# ada2.net
KiCad netlist of a schematic drawn in EAGLE
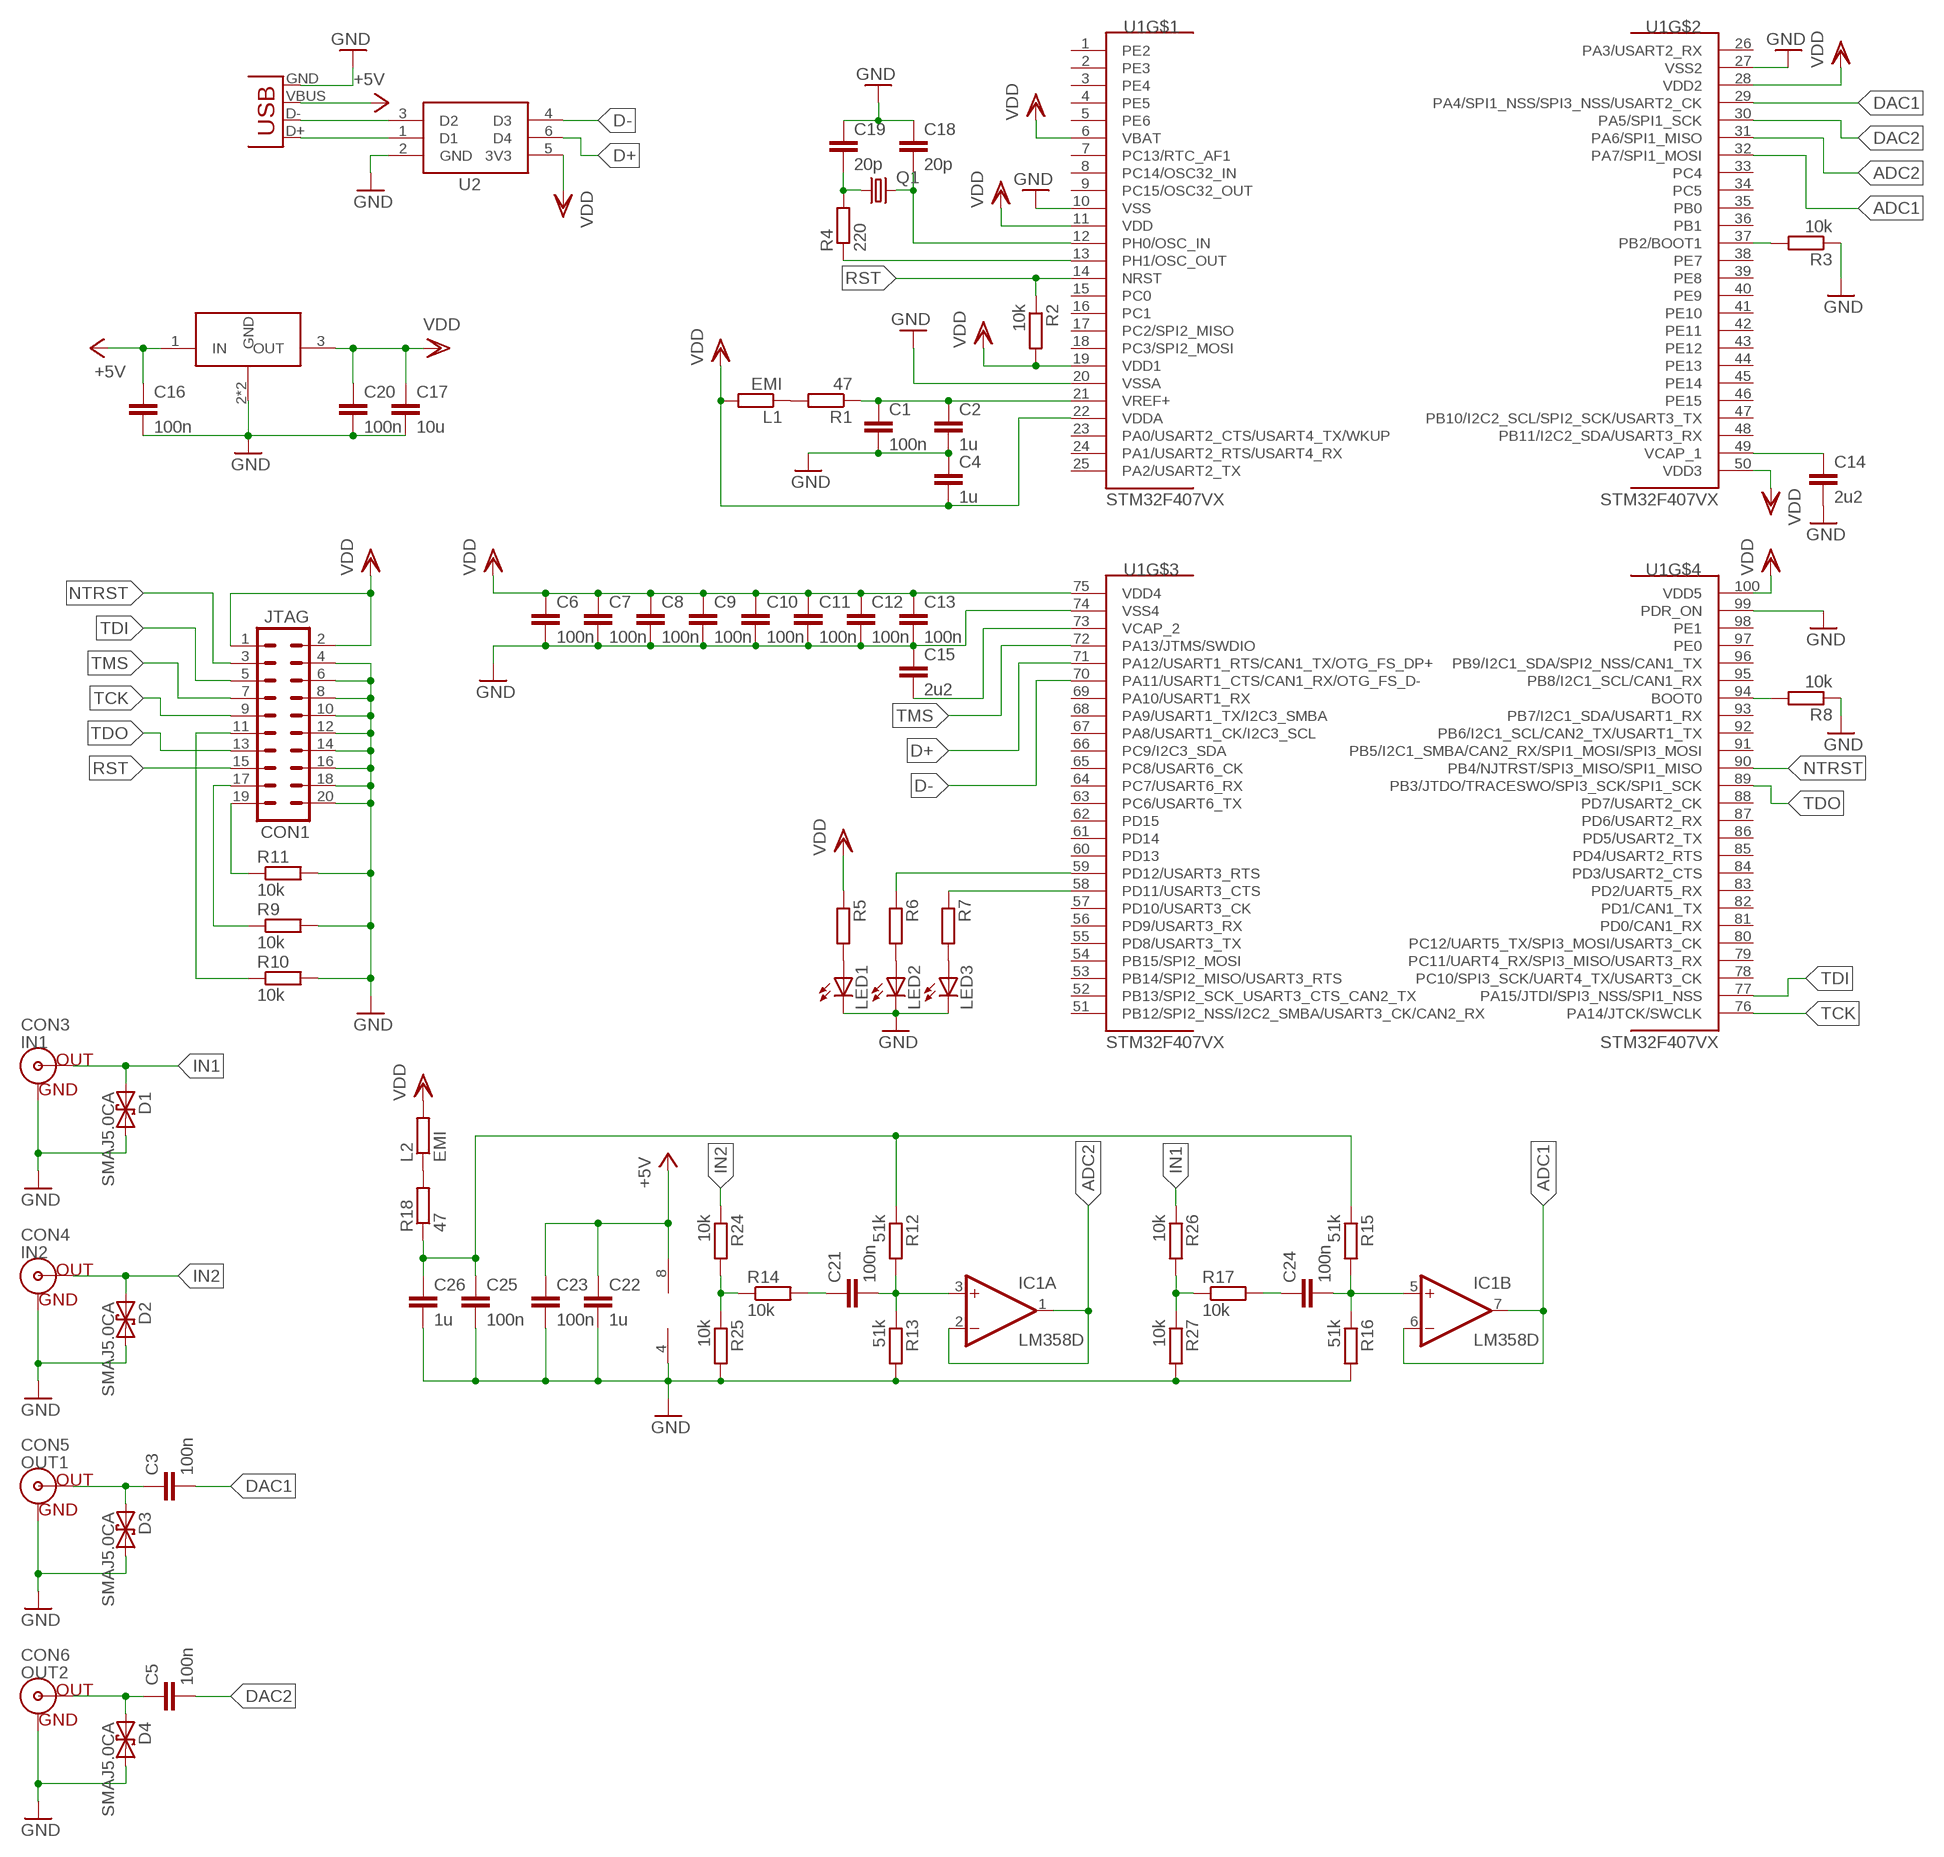
[diagram p0: schematic, sheet 1]

(export (version "E")
  (design (tool "Eeschema 10.0.6"))
  (components
    (comp (ref "C1")
      (value "100n")
      (footprint "eagle-import:C0603K")
      (libsource (lib "eagle-import") (part "C-EUC0603K"))
    )
    (comp (ref "C2")
      (value "1u")
      (footprint "eagle-import:C0603K")
      (libsource (lib "eagle-import") (part "C-EUC0603K"))
    )
    (comp (ref "C3")
      (value "100n")
      (footprint "eagle-import:C0603K")
      (libsource (lib "eagle-import") (part "C-EUC0603K"))
    )
    (comp (ref "C4")
      (value "1u")
      (footprint "eagle-import:C0603K")
      (libsource (lib "eagle-import") (part "C-EUC0603K"))
    )
    (comp (ref "C5")
      (value "100n")
      (footprint "eagle-import:C0603K")
      (libsource (lib "eagle-import") (part "C-EUC0603K"))
    )
    (comp (ref "C6")
      (value "100n")
      (footprint "eagle-import:C0603K")
      (libsource (lib "eagle-import") (part "C-EUC0603K"))
    )
    (comp (ref "C7")
      (value "100n")
      (footprint "eagle-import:C0603K")
      (libsource (lib "eagle-import") (part "C-EUC0603K"))
    )
    (comp (ref "C8")
      (value "100n")
      (footprint "eagle-import:C0603K")
      (libsource (lib "eagle-import") (part "C-EUC0603K"))
    )
    (comp (ref "C9")
      (value "100n")
      (footprint "eagle-import:C0603K")
      (libsource (lib "eagle-import") (part "C-EUC0603K"))
    )
    (comp (ref "C10")
      (value "100n")
      (footprint "eagle-import:C0603K")
      (libsource (lib "eagle-import") (part "C-EUC0603K"))
    )
    (comp (ref "C11")
      (value "100n")
      (footprint "eagle-import:C0603K")
      (libsource (lib "eagle-import") (part "C-EUC0603K"))
    )
    (comp (ref "C12")
      (value "100n")
      (footprint "eagle-import:C0603K")
      (libsource (lib "eagle-import") (part "C-EUC0603K"))
    )
    (comp (ref "C13")
      (value "100n")
      (footprint "eagle-import:C0603K")
      (libsource (lib "eagle-import") (part "C-EUC0603K"))
    )
    (comp (ref "C14")
      (value "2u2")
      (footprint "eagle-import:C0603K")
      (libsource (lib "eagle-import") (part "C-EUC0603K"))
    )
    (comp (ref "C15")
      (value "2u2")
      (footprint "eagle-import:C0603K")
      (libsource (lib "eagle-import") (part "C-EUC0603K"))
    )
    (comp (ref "C16")
      (value "100n")
      (footprint "eagle-import:C0603K")
      (libsource (lib "eagle-import") (part "C-EUC0603K"))
    )
    (comp (ref "C17")
      (value "10u")
      (footprint "eagle-import:C0603K")
      (libsource (lib "eagle-import") (part "C-EUC0603K"))
    )
    (comp (ref "C18")
      (value "20p")
      (footprint "eagle-import:C0603K")
      (libsource (lib "eagle-import") (part "C-EUC0603K"))
    )
    (comp (ref "C19")
      (value "20p")
      (footprint "eagle-import:C0603K")
      (libsource (lib "eagle-import") (part "C-EUC0603K"))
    )
    (comp (ref "C20")
      (value "100n")
      (footprint "eagle-import:C0603K")
      (libsource (lib "eagle-import") (part "C-EUC0603K"))
    )
    (comp (ref "C21")
      (value "100n")
      (footprint "eagle-import:C0603K")
      (libsource (lib "eagle-import") (part "C-EUC0603K"))
    )
    (comp (ref "C22")
      (value "1u")
      (footprint "eagle-import:C0603K")
      (libsource (lib "eagle-import") (part "C-EUC0603K"))
    )
    (comp (ref "C23")
      (value "100n")
      (footprint "eagle-import:C0603K")
      (libsource (lib "eagle-import") (part "C-EUC0603K"))
    )
    (comp (ref "C24")
      (value "100n")
      (footprint "eagle-import:C0603K")
      (libsource (lib "eagle-import") (part "C-EUC0603K"))
    )
    (comp (ref "C25")
      (value "100n")
      (footprint "eagle-import:C0603K")
      (libsource (lib "eagle-import") (part "C-EUC0603K"))
    )
    (comp (ref "C26")
      (value "1u")
      (footprint "eagle-import:C0603K")
      (libsource (lib "eagle-import") (part "C-EUC0603K"))
    )
    (comp (ref "CON1")
      (value "JTAG")
      (footprint "eagle-import:ML20")
      (libsource (lib "eagle-import") (part "ML20"))
    )
    (comp (ref "CON2")
      (value "USB-B")
      (footprint "eagle-import:USB-B-PTH")
      (libsource (lib "eagle-import") (part "USBPTH"))
    )
    (comp (ref "CON3")
      (value "IN1")
      (footprint "eagle-import:BNC")
      (libsource (lib "eagle-import") (part "BNCPTH"))
    )
    (comp (ref "CON4")
      (value "IN2")
      (footprint "eagle-import:BNC")
      (libsource (lib "eagle-import") (part "BNCPTH"))
    )
    (comp (ref "CON5")
      (value "OUT1")
      (footprint "eagle-import:BNC")
      (libsource (lib "eagle-import") (part "BNCPTH"))
    )
    (comp (ref "CON6")
      (value "OUT2")
      (footprint "eagle-import:BNC")
      (libsource (lib "eagle-import") (part "BNCPTH"))
    )
    (comp (ref "D1")
      (value "SMAJ5.0CA")
      (footprint "eagle-import:SMA-DIODE")
      (libsource (lib "eagle-import") (part "TVS"))
    )
    (comp (ref "D2")
      (value "SMAJ5.0CA")
      (footprint "eagle-import:SMA-DIODE")
      (libsource (lib "eagle-import") (part "TVS"))
    )
    (comp (ref "D3")
      (value "SMAJ5.0CA")
      (footprint "eagle-import:SMA-DIODE")
      (libsource (lib "eagle-import") (part "TVS"))
    )
    (comp (ref "D4")
      (value "SMAJ5.0CA")
      (footprint "eagle-import:SMA-DIODE")
      (libsource (lib "eagle-import") (part "TVS"))
    )
    (comp (ref "IC1")
      (value "LM358D")
      (footprint "eagle-import:SO08")
      (libsource (lib "eagle-import") (part "LM358D"))
    )
    (comp (ref "L1")
      (value "EMI")
      (footprint "eagle-import:R0603")
      (libsource (lib "eagle-import") (part "R-EU_R0603"))
    )
    (comp (ref "L2")
      (value "EMI")
      (footprint "eagle-import:R0603")
      (libsource (lib "eagle-import") (part "R-EU_R0603"))
    )
    (comp (ref "LED1")
      (value "KONTROLKA_LED")
      (footprint "eagle-import:KONTROLKA_LED")
      (libsource (lib "eagle-import") (part "KONTROLKA_LED"))
    )
    (comp (ref "LED2")
      (value "KONTROLKA_LED")
      (footprint "eagle-import:KONTROLKA_LED")
      (libsource (lib "eagle-import") (part "KONTROLKA_LED"))
    )
    (comp (ref "LED3")
      (value "KONTROLKA_LED")
      (footprint "eagle-import:KONTROLKA_LED")
      (libsource (lib "eagle-import") (part "KONTROLKA_LED"))
    )
    (comp (ref "Q1")
      (value "CRYSTALHC49UP")
      (footprint "eagle-import:HC49UP")
      (libsource (lib "eagle-import") (part "CRYSTALHC49UP"))
    )
    (comp (ref "R1")
      (value "47")
      (footprint "eagle-import:R0603")
      (libsource (lib "eagle-import") (part "R-EU_R0603"))
    )
    (comp (ref "R2")
      (value "10k")
      (footprint "eagle-import:R0603")
      (libsource (lib "eagle-import") (part "R-EU_R0603"))
    )
    (comp (ref "R3")
      (value "10k")
      (footprint "eagle-import:R0603")
      (libsource (lib "eagle-import") (part "R-EU_R0603"))
    )
    (comp (ref "R4")
      (value "220")
      (footprint "eagle-import:R0603")
      (libsource (lib "eagle-import") (part "R-EU_R0603"))
    )
    (comp (ref "R5")
      (value "R-EU_R0603")
      (footprint "eagle-import:R0603")
      (libsource (lib "eagle-import") (part "R-EU_R0603"))
    )
    (comp (ref "R6")
      (value "R-EU_R0603")
      (footprint "eagle-import:R0603")
      (libsource (lib "eagle-import") (part "R-EU_R0603"))
    )
    (comp (ref "R7")
      (value "R-EU_R0603")
      (footprint "eagle-import:R0603")
      (libsource (lib "eagle-import") (part "R-EU_R0603"))
    )
    (comp (ref "R8")
      (value "10k")
      (footprint "eagle-import:R0603")
      (libsource (lib "eagle-import") (part "R-EU_R0603"))
    )
    (comp (ref "R9")
      (value "10k")
      (footprint "eagle-import:R0603")
      (libsource (lib "eagle-import") (part "R-EU_R0603"))
    )
    (comp (ref "R10")
      (value "10k")
      (footprint "eagle-import:R0603")
      (libsource (lib "eagle-import") (part "R-EU_R0603"))
    )
    (comp (ref "R11")
      (value "10k")
      (footprint "eagle-import:R0603")
      (libsource (lib "eagle-import") (part "R-EU_R0603"))
    )
    (comp (ref "R12")
      (value "51k")
      (footprint "eagle-import:R0603")
      (libsource (lib "eagle-import") (part "R-EU_R0603"))
    )
    (comp (ref "R13")
      (value "51k")
      (footprint "eagle-import:R0603")
      (libsource (lib "eagle-import") (part "R-EU_R0603"))
    )
    (comp (ref "R14")
      (value "10k")
      (footprint "eagle-import:R0603")
      (libsource (lib "eagle-import") (part "R-EU_R0603"))
    )
    (comp (ref "R15")
      (value "51k")
      (footprint "eagle-import:R0603")
      (libsource (lib "eagle-import") (part "R-EU_R0603"))
    )
    (comp (ref "R16")
      (value "51k")
      (footprint "eagle-import:R0603")
      (libsource (lib "eagle-import") (part "R-EU_R0603"))
    )
    (comp (ref "R17")
      (value "10k")
      (footprint "eagle-import:R0603")
      (libsource (lib "eagle-import") (part "R-EU_R0603"))
    )
    (comp (ref "R18")
      (value "47")
      (footprint "eagle-import:R0603")
      (libsource (lib "eagle-import") (part "R-EU_R0603"))
    )
    (comp (ref "R24")
      (value "10k")
      (footprint "eagle-import:R0603")
      (libsource (lib "eagle-import") (part "R-EU_R0603"))
    )
    (comp (ref "R25")
      (value "10k")
      (footprint "eagle-import:R0603")
      (libsource (lib "eagle-import") (part "R-EU_R0603"))
    )
    (comp (ref "R26")
      (value "10k")
      (footprint "eagle-import:R0603")
      (libsource (lib "eagle-import") (part "R-EU_R0603"))
    )
    (comp (ref "R27")
      (value "10k")
      (footprint "eagle-import:R0603")
      (libsource (lib "eagle-import") (part "R-EU_R0603"))
    )
    (comp (ref "U1")
      (value "STM32F407VX")
      (footprint "eagle-import:LQFP100")
      (libsource (lib "eagle-import") (part "STM32F407VX"))
    )
    (comp (ref "U2")
      (value "USBUF01W6")
      (footprint "eagle-import:SOT363")
      (libsource (lib "eagle-import") (part "USBUF01W6"))
    )
    (comp (ref "U3")
      (value "MCP1703")
      (footprint "eagle-import:SOT223")
      (libsource (lib "eagle-import") (part "MCP1703"))
    )
  )
  (nets
    (net (code "1") (name "+5V") (class "Default")
      (node (ref "C16") (pin "1") (pinfunction "1_1") (pintype "passive"))
      (node (ref "C22") (pin "1") (pinfunction "1_1") (pintype "passive"))
      (node (ref "C23") (pin "1") (pinfunction "1_1") (pintype "passive"))
      (node (ref "CON2") (pin "VBUS") (pinfunction "VBUS_VBUS") (pintype "bidirectional"))
      (node (ref "IC1") (pin "8") (pinfunction "V+_8") (pintype "power_in"))
      (node (ref "U3") (pin "1") (pinfunction "IN_1") (pintype "bidirectional"))
    )
    (net (code "2") (name "ADC1") (class "Default")
      (node (ref "IC1") (pin "6") (pinfunction "-IN_6") (pintype "input"))
      (node (ref "IC1") (pin "7") (pinfunction "OUT_7") (pintype "output"))
      (node (ref "U1") (pin "32") (pinfunction "PA7/SPI1_MOSI_32") (pintype "bidirectional"))
    )
    (net (code "3") (name "ADC2") (class "Default")
      (node (ref "IC1") (pin "1") (pinfunction "OUT_1") (pintype "output"))
      (node (ref "IC1") (pin "2") (pinfunction "-IN_2") (pintype "input"))
      (node (ref "U1") (pin "31") (pinfunction "PA6/SPI1_MISO_31") (pintype "bidirectional"))
    )
    (net (code "4") (name "D+") (class "Default")
      (node (ref "U1") (pin "71") (pinfunction "PA12/USART1_RTS/CAN1_TX/OTG_FS_DP+_71") (pintype "bidirectional"))
      (node (ref "U2") (pin "6") (pinfunction "D4_6") (pintype "bidirectional"))
    )
    (net (code "5") (name "D-") (class "Default")
      (node (ref "U1") (pin "70") (pinfunction "PA11/USART1_CTS/CAN1_RX/OTG_FS_D-_70") (pintype "bidirectional"))
      (node (ref "U2") (pin "4") (pinfunction "D3_4") (pintype "bidirectional"))
    )
    (net (code "6") (name "DAC1") (class "Default")
      (node (ref "C3") (pin "2") (pinfunction "2_2") (pintype "passive"))
      (node (ref "U1") (pin "29") (pinfunction "PA4/SPI1_NSS/SPI3_NSS/USART2_CK_29") (pintype "bidirectional"))
    )
    (net (code "7") (name "DAC2") (class "Default")
      (node (ref "C5") (pin "2") (pinfunction "2_2") (pintype "passive"))
      (node (ref "U1") (pin "30") (pinfunction "PA5/SPI1_SCK_30") (pintype "bidirectional"))
    )
    (net (code "8") (name "GND") (class "Default")
      (node (ref "C1") (pin "2") (pinfunction "2_2") (pintype "passive"))
      (node (ref "C10") (pin "2") (pinfunction "2_2") (pintype "passive"))
      (node (ref "C11") (pin "2") (pinfunction "2_2") (pintype "passive"))
      (node (ref "C12") (pin "2") (pinfunction "2_2") (pintype "passive"))
      (node (ref "C13") (pin "2") (pinfunction "2_2") (pintype "passive"))
      (node (ref "C14") (pin "2") (pinfunction "2_2") (pintype "passive"))
      (node (ref "C15") (pin "1") (pinfunction "1_1") (pintype "passive"))
      (node (ref "C16") (pin "2") (pinfunction "2_2") (pintype "passive"))
      (node (ref "C17") (pin "2") (pinfunction "2_2") (pintype "passive"))
      (node (ref "C18") (pin "1") (pinfunction "1_1") (pintype "passive"))
      (node (ref "C19") (pin "1") (pinfunction "1_1") (pintype "passive"))
      (node (ref "C2") (pin "2") (pinfunction "2_2") (pintype "passive"))
      (node (ref "C20") (pin "2") (pinfunction "2_2") (pintype "passive"))
      (node (ref "C22") (pin "2") (pinfunction "2_2") (pintype "passive"))
      (node (ref "C23") (pin "2") (pinfunction "2_2") (pintype "passive"))
      (node (ref "C25") (pin "2") (pinfunction "2_2") (pintype "passive"))
      (node (ref "C26") (pin "2") (pinfunction "2_2") (pintype "passive"))
      (node (ref "C4") (pin "1") (pinfunction "1_1") (pintype "passive"))
      (node (ref "C6") (pin "2") (pinfunction "2_2") (pintype "passive"))
      (node (ref "C7") (pin "2") (pinfunction "2_2") (pintype "passive"))
      (node (ref "C8") (pin "2") (pinfunction "2_2") (pintype "passive"))
      (node (ref "C9") (pin "2") (pinfunction "2_2") (pintype "passive"))
      (node (ref "CON1") (pin "10") (pinfunction "10_10") (pintype "passive"))
      (node (ref "CON1") (pin "12") (pinfunction "12_12") (pintype "passive"))
      (node (ref "CON1") (pin "14") (pinfunction "14_14") (pintype "passive"))
      (node (ref "CON1") (pin "16") (pinfunction "16_16") (pintype "passive"))
      (node (ref "CON1") (pin "18") (pinfunction "18_18") (pintype "passive"))
      (node (ref "CON1") (pin "20") (pinfunction "20_20") (pintype "passive"))
      (node (ref "CON1") (pin "4") (pinfunction "4_4") (pintype "passive"))
      (node (ref "CON1") (pin "6") (pinfunction "6_6") (pintype "passive"))
      (node (ref "CON1") (pin "8") (pinfunction "8_8") (pintype "passive"))
      (node (ref "CON2") (pin "GND") (pinfunction "GND_GND") (pintype "bidirectional"))
      (node (ref "CON3") (pin "GND") (pinfunction "GND_GND") (pintype "bidirectional"))
      (node (ref "CON4") (pin "GND") (pinfunction "GND_GND") (pintype "bidirectional"))
      (node (ref "CON5") (pin "GND") (pinfunction "GND_GND") (pintype "bidirectional"))
      (node (ref "CON6") (pin "GND") (pinfunction "GND_GND") (pintype "bidirectional"))
      (node (ref "D1") (pin "C") (pinfunction "2_C") (pintype "passive"))
      (node (ref "D2") (pin "C") (pinfunction "2_C") (pintype "passive"))
      (node (ref "D3") (pin "C") (pinfunction "2_C") (pintype "passive"))
      (node (ref "D4") (pin "C") (pinfunction "2_C") (pintype "passive"))
      (node (ref "IC1") (pin "4") (pinfunction "V-_4") (pintype "power_in"))
      (node (ref "LED1") (pin "K") (pinfunction "C_K") (pintype "passive"))
      (node (ref "LED2") (pin "K") (pinfunction "C_K") (pintype "passive"))
      (node (ref "LED3") (pin "K") (pinfunction "C_K") (pintype "passive"))
      (node (ref "R10") (pin "2") (pinfunction "2_2") (pintype "passive"))
      (node (ref "R11") (pin "2") (pinfunction "2_2") (pintype "passive"))
      (node (ref "R13") (pin "2") (pinfunction "2_2") (pintype "passive"))
      (node (ref "R16") (pin "2") (pinfunction "2_2") (pintype "passive"))
      (node (ref "R25") (pin "2") (pinfunction "2_2") (pintype "passive"))
      (node (ref "R27") (pin "2") (pinfunction "2_2") (pintype "passive"))
      (node (ref "R3") (pin "1") (pinfunction "1_1") (pintype "passive"))
      (node (ref "R8") (pin "1") (pinfunction "1_1") (pintype "passive"))
      (node (ref "R9") (pin "2") (pinfunction "2_2") (pintype "passive"))
      (node (ref "U1") (pin "10") (pinfunction "VSS_10") (pintype "bidirectional"))
      (node (ref "U1") (pin "20") (pinfunction "VSSA_20") (pintype "bidirectional"))
      (node (ref "U1") (pin "27") (pinfunction "VSS2_27") (pintype "bidirectional"))
      (node (ref "U1") (pin "74") (pinfunction "VSS4_74") (pintype "bidirectional"))
      (node (ref "U1") (pin "99") (pinfunction "PDR_ON_99") (pintype "bidirectional"))
      (node (ref "U2") (pin "2") (pinfunction "GND_2") (pintype "bidirectional"))
      (node (ref "U3") (pin "2") (pinfunction "GND_2") (pintype "bidirectional"))
      (node (ref "U3") (pin "2@2") (pinfunction "GND_2@2") (pintype "bidirectional"))
    )
    (net (code "9") (name "IN1") (class "Default")
      (node (ref "CON3") (pin "S") (pinfunction "OUT_S") (pintype "bidirectional"))
      (node (ref "D1") (pin "A") (pinfunction "1_A") (pintype "passive"))
      (node (ref "R26") (pin "1") (pinfunction "1_1") (pintype "passive"))
    )
    (net (code "10") (name "IN2") (class "Default")
      (node (ref "CON4") (pin "S") (pinfunction "OUT_S") (pintype "bidirectional"))
      (node (ref "D2") (pin "A") (pinfunction "1_A") (pintype "passive"))
      (node (ref "R24") (pin "1") (pinfunction "1_1") (pintype "passive"))
    )
    (net (code "11") (name "NTRST") (class "Default")
      (node (ref "CON1") (pin "3") (pinfunction "3_3") (pintype "passive"))
      (node (ref "U1") (pin "90") (pinfunction "PB4/NJTRST/SPI3_MISO/SPI1_MISO_90") (pintype "bidirectional"))
    )
    (net (code "12") (name "Net-(C19-Pad2)") (class "Default")
      (node (ref "C19") (pin "2") (pinfunction "2_2") (pintype "passive"))
      (node (ref "Q1") (pin "1") (pinfunction "1_1") (pintype "passive"))
      (node (ref "R4") (pin "2") (pinfunction "2_2") (pintype "passive"))
    )
    (net (code "13") (name "Net-(C21-Pad1)") (class "Default")
      (node (ref "C21") (pin "1") (pinfunction "1_1") (pintype "passive"))
      (node (ref "R14") (pin "2") (pinfunction "2_2") (pintype "passive"))
    )
    (net (code "14") (name "Net-(C24-Pad1)") (class "Default")
      (node (ref "C24") (pin "1") (pinfunction "1_1") (pintype "passive"))
      (node (ref "R17") (pin "2") (pinfunction "2_2") (pintype "passive"))
    )
    (net (code "15") (name "Net-(C25-Pad1)") (class "Default")
      (node (ref "C25") (pin "1") (pinfunction "1_1") (pintype "passive"))
      (node (ref "C26") (pin "1") (pinfunction "1_1") (pintype "passive"))
      (node (ref "R12") (pin "1") (pinfunction "1_1") (pintype "passive"))
      (node (ref "R15") (pin "1") (pinfunction "1_1") (pintype "passive"))
      (node (ref "R18") (pin "1") (pinfunction "1_1") (pintype "passive"))
    )
    (net (code "16") (name "Net-(CON1-Pad11)") (class "Default")
      (node (ref "CON1") (pin "11") (pinfunction "11_11") (pintype "passive"))
      (node (ref "R10") (pin "1") (pinfunction "1_1") (pintype "passive"))
    )
    (net (code "17") (name "Net-(CON1-Pad17)") (class "Default")
      (node (ref "CON1") (pin "17") (pinfunction "17_17") (pintype "passive"))
      (node (ref "R9") (pin "1") (pinfunction "1_1") (pintype "passive"))
    )
    (net (code "18") (name "Net-(CON1-Pad19)") (class "Default")
      (node (ref "CON1") (pin "19") (pinfunction "19_19") (pintype "passive"))
      (node (ref "R11") (pin "1") (pinfunction "1_1") (pintype "passive"))
    )
    (net (code "19") (name "Net-(CON5-OUT)") (class "Default")
      (node (ref "C3") (pin "1") (pinfunction "1_1") (pintype "passive"))
      (node (ref "CON5") (pin "S") (pinfunction "OUT_S") (pintype "bidirectional"))
      (node (ref "D3") (pin "A") (pinfunction "1_A") (pintype "passive"))
    )
    (net (code "20") (name "Net-(CON6-OUT)") (class "Default")
      (node (ref "C5") (pin "1") (pinfunction "1_1") (pintype "passive"))
      (node (ref "CON6") (pin "S") (pinfunction "OUT_S") (pintype "bidirectional"))
      (node (ref "D4") (pin "A") (pinfunction "1_A") (pintype "passive"))
    )
    (net (code "21") (name "Net-(IC1A-+IN)") (class "Default")
      (node (ref "C21") (pin "2") (pinfunction "2_2") (pintype "passive"))
      (node (ref "IC1") (pin "3") (pinfunction "+IN_3") (pintype "input"))
      (node (ref "R12") (pin "2") (pinfunction "2_2") (pintype "passive"))
      (node (ref "R13") (pin "1") (pinfunction "1_1") (pintype "passive"))
    )
    (net (code "22") (name "Net-(IC1B-+IN)") (class "Default")
      (node (ref "C24") (pin "2") (pinfunction "2_2") (pintype "passive"))
      (node (ref "IC1") (pin "5") (pinfunction "+IN_5") (pintype "input"))
      (node (ref "R15") (pin "2") (pinfunction "2_2") (pintype "passive"))
      (node (ref "R16") (pin "1") (pinfunction "1_1") (pintype "passive"))
    )
    (net (code "23") (name "Net-(L1-Pad1)") (class "Default")
      (node (ref "L1") (pin "1") (pinfunction "1_1") (pintype "passive"))
      (node (ref "R1") (pin "2") (pinfunction "2_2") (pintype "passive"))
    )
    (net (code "24") (name "Net-(L2-Pad1)") (class "Default")
      (node (ref "L2") (pin "1") (pinfunction "1_1") (pintype "passive"))
      (node (ref "R18") (pin "2") (pinfunction "2_2") (pintype "passive"))
    )
    (net (code "25") (name "Net-(LED1-PadA)") (class "Default")
      (node (ref "LED1") (pin "A") (pinfunction "A_A") (pintype "passive"))
      (node (ref "R5") (pin "2") (pinfunction "2_2") (pintype "passive"))
    )
    (net (code "26") (name "Net-(LED2-PadA)") (class "Default")
      (node (ref "LED2") (pin "A") (pinfunction "A_A") (pintype "passive"))
      (node (ref "R6") (pin "2") (pinfunction "2_2") (pintype "passive"))
    )
    (net (code "27") (name "Net-(LED3-PadA)") (class "Default")
      (node (ref "LED3") (pin "A") (pinfunction "A_A") (pintype "passive"))
      (node (ref "R7") (pin "2") (pinfunction "2_2") (pintype "passive"))
    )
    (net (code "28") (name "Net-(R14-Pad1)") (class "Default")
      (node (ref "R14") (pin "1") (pinfunction "1_1") (pintype "passive"))
      (node (ref "R24") (pin "2") (pinfunction "2_2") (pintype "passive"))
      (node (ref "R25") (pin "1") (pinfunction "1_1") (pintype "passive"))
    )
    (net (code "29") (name "Net-(R17-Pad1)") (class "Default")
      (node (ref "R17") (pin "1") (pinfunction "1_1") (pintype "passive"))
      (node (ref "R26") (pin "2") (pinfunction "2_2") (pintype "passive"))
      (node (ref "R27") (pin "1") (pinfunction "1_1") (pintype "passive"))
    )
    (net (code "30") (name "Net-(U1A-PH0{slash}OSC_IN)") (class "Default")
      (node (ref "C18") (pin "2") (pinfunction "2_2") (pintype "passive"))
      (node (ref "Q1") (pin "2") (pinfunction "2_2") (pintype "passive"))
      (node (ref "U1") (pin "12") (pinfunction "PH0/OSC_IN_12") (pintype "bidirectional"))
    )
    (net (code "31") (name "Net-(U1A-PH1{slash}OSC_OUT)") (class "Default")
      (node (ref "R4") (pin "1") (pinfunction "1_1") (pintype "passive"))
      (node (ref "U1") (pin "13") (pinfunction "PH1/OSC_OUT_13") (pintype "bidirectional"))
    )
    (net (code "32") (name "Net-(U1A-VREF+)") (class "Default")
      (node (ref "C1") (pin "1") (pinfunction "1_1") (pintype "passive"))
      (node (ref "C2") (pin "1") (pinfunction "1_1") (pintype "passive"))
      (node (ref "R1") (pin "1") (pinfunction "1_1") (pintype "passive"))
      (node (ref "U1") (pin "21") (pinfunction "VREF+_21") (pintype "bidirectional"))
    )
    (net (code "33") (name "Net-(U1B-PB2{slash}BOOT1)") (class "Default")
      (node (ref "R3") (pin "2") (pinfunction "2_2") (pintype "passive"))
      (node (ref "U1") (pin "37") (pinfunction "PB2/BOOT1_37") (pintype "bidirectional"))
    )
    (net (code "34") (name "Net-(U1B-VCAP_1)") (class "Default")
      (node (ref "C14") (pin "1") (pinfunction "1_1") (pintype "passive"))
      (node (ref "U1") (pin "49") (pinfunction "VCAP_1_49") (pintype "bidirectional"))
    )
    (net (code "35") (name "Net-(U1C-PD11{slash}USART3_CTS)") (class "Default")
      (node (ref "R7") (pin "1") (pinfunction "1_1") (pintype "passive"))
      (node (ref "U1") (pin "58") (pinfunction "PD11/USART3_CTS_58") (pintype "bidirectional"))
    )
    (net (code "36") (name "Net-(U1C-PD12{slash}USART3_RTS)") (class "Default")
      (node (ref "R6") (pin "1") (pinfunction "1_1") (pintype "passive"))
      (node (ref "U1") (pin "59") (pinfunction "PD12/USART3_RTS_59") (pintype "bidirectional"))
    )
    (net (code "37") (name "Net-(U1C-VCAP_2)") (class "Default")
      (node (ref "C15") (pin "2") (pinfunction "2_2") (pintype "passive"))
      (node (ref "U1") (pin "73") (pinfunction "VCAP_2_73") (pintype "bidirectional"))
    )
    (net (code "38") (name "Net-(U1D-BOOT0)") (class "Default")
      (node (ref "R8") (pin "2") (pinfunction "2_2") (pintype "passive"))
      (node (ref "U1") (pin "94") (pinfunction "BOOT0_94") (pintype "bidirectional"))
    )
    (net (code "39") (name "Net-(U2-D1)") (class "Default")
      (node (ref "CON2") (pin "D+") (pinfunction "D+_D+") (pintype "bidirectional"))
      (node (ref "U2") (pin "1") (pinfunction "D1_1") (pintype "bidirectional"))
    )
    (net (code "40") (name "Net-(U2-D2)") (class "Default")
      (node (ref "CON2") (pin "D-") (pinfunction "D-_D-") (pintype "bidirectional"))
      (node (ref "U2") (pin "3") (pinfunction "D2_3") (pintype "bidirectional"))
    )
    (net (code "41") (name "RST") (class "Default")
      (node (ref "CON1") (pin "15") (pinfunction "15_15") (pintype "passive"))
      (node (ref "R2") (pin "1") (pinfunction "1_1") (pintype "passive"))
      (node (ref "U1") (pin "14") (pinfunction "NRST_14") (pintype "bidirectional"))
    )
    (net (code "42") (name "TCK") (class "Default")
      (node (ref "CON1") (pin "9") (pinfunction "9_9") (pintype "passive"))
      (node (ref "U1") (pin "76") (pinfunction "PA14/JTCK/SWCLK_76") (pintype "bidirectional"))
    )
    (net (code "43") (name "TDI") (class "Default")
      (node (ref "CON1") (pin "5") (pinfunction "5_5") (pintype "passive"))
      (node (ref "U1") (pin "77") (pinfunction "PA15/JTDI/SPI3_NSS/SPI1_NSS_77") (pintype "bidirectional"))
    )
    (net (code "44") (name "TDO") (class "Default")
      (node (ref "CON1") (pin "13") (pinfunction "13_13") (pintype "passive"))
      (node (ref "U1") (pin "89") (pinfunction "PB3/JTDO/TRACESWO/SPI3_SCK/SPI1_SCK_89") (pintype "bidirectional"))
    )
    (net (code "45") (name "TMS") (class "Default")
      (node (ref "CON1") (pin "7") (pinfunction "7_7") (pintype "passive"))
      (node (ref "U1") (pin "72") (pinfunction "PA13/JTMS/SWDIO_72") (pintype "bidirectional"))
    )
    (net (code "46") (name "VDD") (class "Default")
      (node (ref "C10") (pin "1") (pinfunction "1_1") (pintype "passive"))
      (node (ref "C11") (pin "1") (pinfunction "1_1") (pintype "passive"))
      (node (ref "C12") (pin "1") (pinfunction "1_1") (pintype "passive"))
      (node (ref "C13") (pin "1") (pinfunction "1_1") (pintype "passive"))
      (node (ref "C17") (pin "1") (pinfunction "1_1") (pintype "passive"))
      (node (ref "C20") (pin "1") (pinfunction "1_1") (pintype "passive"))
      (node (ref "C4") (pin "2") (pinfunction "2_2") (pintype "passive"))
      (node (ref "C6") (pin "1") (pinfunction "1_1") (pintype "passive"))
      (node (ref "C7") (pin "1") (pinfunction "1_1") (pintype "passive"))
      (node (ref "C8") (pin "1") (pinfunction "1_1") (pintype "passive"))
      (node (ref "C9") (pin "1") (pinfunction "1_1") (pintype "passive"))
      (node (ref "CON1") (pin "1") (pinfunction "1_1") (pintype "passive"))
      (node (ref "CON1") (pin "2") (pinfunction "2_2") (pintype "passive"))
      (node (ref "L1") (pin "2") (pinfunction "2_2") (pintype "passive"))
      (node (ref "L2") (pin "2") (pinfunction "2_2") (pintype "passive"))
      (node (ref "R2") (pin "2") (pinfunction "2_2") (pintype "passive"))
      (node (ref "R5") (pin "1") (pinfunction "1_1") (pintype "passive"))
      (node (ref "U1") (pin "100") (pinfunction "VDD5_100") (pintype "bidirectional"))
      (node (ref "U1") (pin "11") (pinfunction "VDD_11") (pintype "bidirectional"))
      (node (ref "U1") (pin "19") (pinfunction "VDD1_19") (pintype "bidirectional"))
      (node (ref "U1") (pin "22") (pinfunction "VDDA_22") (pintype "bidirectional"))
      (node (ref "U1") (pin "28") (pinfunction "VDD2_28") (pintype "bidirectional"))
      (node (ref "U1") (pin "50") (pinfunction "VDD3_50") (pintype "bidirectional"))
      (node (ref "U1") (pin "6") (pinfunction "VBAT_6") (pintype "bidirectional"))
      (node (ref "U1") (pin "75") (pinfunction "VDD4_75") (pintype "bidirectional"))
      (node (ref "U2") (pin "5") (pinfunction "3V3_5") (pintype "bidirectional"))
      (node (ref "U3") (pin "3") (pinfunction "OUT_3") (pintype "bidirectional"))
    )
    (net (code "47") (name "unconnected-(U1A-PA0{slash}USART2_CTS{slash}USART4_TX{slash}WKUP-Pad23)") (class "Default")
      (node (ref "U1") (pin "23") (pinfunction "PA0/USART2_CTS/USART4_TX/WKUP_23") (pintype "bidirectional"))
    )
    (net (code "48") (name "unconnected-(U1A-PA1{slash}USART2_RTS{slash}USART4_RX-Pad24)") (class "Default")
      (node (ref "U1") (pin "24") (pinfunction "PA1/USART2_RTS/USART4_RX_24") (pintype "bidirectional"))
    )
    (net (code "49") (name "unconnected-(U1A-PA2{slash}USART2_TX-Pad25)") (class "Default")
      (node (ref "U1") (pin "25") (pinfunction "PA2/USART2_TX_25") (pintype "bidirectional"))
    )
    (net (code "50") (name "unconnected-(U1A-PC0-Pad15)") (class "Default")
      (node (ref "U1") (pin "15") (pinfunction "PC0_15") (pintype "bidirectional"))
    )
    (net (code "51") (name "unconnected-(U1A-PC1-Pad16)") (class "Default")
      (node (ref "U1") (pin "16") (pinfunction "PC1_16") (pintype "bidirectional"))
    )
    (net (code "52") (name "unconnected-(U1A-PC2{slash}SPI2_MISO-Pad17)") (class "Default")
      (node (ref "U1") (pin "17") (pinfunction "PC2/SPI2_MISO_17") (pintype "bidirectional"))
    )
    (net (code "53") (name "unconnected-(U1A-PC3{slash}SPI2_MOSI-Pad18)") (class "Default")
      (node (ref "U1") (pin "18") (pinfunction "PC3/SPI2_MOSI_18") (pintype "bidirectional"))
    )
    (net (code "54") (name "unconnected-(U1A-PC13{slash}RTC_AF1-Pad7)") (class "Default")
      (node (ref "U1") (pin "7") (pinfunction "PC13/RTC_AF1_7") (pintype "bidirectional"))
    )
    (net (code "55") (name "unconnected-(U1A-PC14{slash}OSC32_IN-Pad8)") (class "Default")
      (node (ref "U1") (pin "8") (pinfunction "PC14/OSC32_IN_8") (pintype "bidirectional"))
    )
    (net (code "56") (name "unconnected-(U1A-PC15{slash}OSC32_OUT-Pad9)") (class "Default")
      (node (ref "U1") (pin "9") (pinfunction "PC15/OSC32_OUT_9") (pintype "bidirectional"))
    )
    (net (code "57") (name "unconnected-(U1A-PE2-Pad1)") (class "Default")
      (node (ref "U1") (pin "1") (pinfunction "PE2_1") (pintype "bidirectional"))
    )
    (net (code "58") (name "unconnected-(U1A-PE3-Pad2)") (class "Default")
      (node (ref "U1") (pin "2") (pinfunction "PE3_2") (pintype "bidirectional"))
    )
    (net (code "59") (name "unconnected-(U1A-PE4-Pad3)") (class "Default")
      (node (ref "U1") (pin "3") (pinfunction "PE4_3") (pintype "bidirectional"))
    )
    (net (code "60") (name "unconnected-(U1A-PE5-Pad4)") (class "Default")
      (node (ref "U1") (pin "4") (pinfunction "PE5_4") (pintype "bidirectional"))
    )
    (net (code "61") (name "unconnected-(U1A-PE6-Pad5)") (class "Default")
      (node (ref "U1") (pin "5") (pinfunction "PE6_5") (pintype "bidirectional"))
    )
    (net (code "62") (name "unconnected-(U1B-PA3{slash}USART2_RX-Pad26)") (class "Default")
      (node (ref "U1") (pin "26") (pinfunction "PA3/USART2_RX_26") (pintype "bidirectional"))
    )
    (net (code "63") (name "unconnected-(U1B-PB0-Pad35)") (class "Default")
      (node (ref "U1") (pin "35") (pinfunction "PB0_35") (pintype "bidirectional"))
    )
    (net (code "64") (name "unconnected-(U1B-PB1-Pad36)") (class "Default")
      (node (ref "U1") (pin "36") (pinfunction "PB1_36") (pintype "bidirectional"))
    )
    (net (code "65") (name "unconnected-(U1B-PB10{slash}I2C2_SCL{slash}SPI2_SCK{slash}USART3_TX-Pad47)") (class "Default")
      (node (ref "U1") (pin "47") (pinfunction "PB10/I2C2_SCL/SPI2_SCK/USART3_TX_47") (pintype "bidirectional"))
    )
    (net (code "66") (name "unconnected-(U1B-PB11{slash}I2C2_SDA{slash}USART3_RX-Pad48)") (class "Default")
      (node (ref "U1") (pin "48") (pinfunction "PB11/I2C2_SDA/USART3_RX_48") (pintype "bidirectional"))
    )
    (net (code "67") (name "unconnected-(U1B-PC4-Pad33)") (class "Default")
      (node (ref "U1") (pin "33") (pinfunction "PC4_33") (pintype "bidirectional"))
    )
    (net (code "68") (name "unconnected-(U1B-PC5-Pad34)") (class "Default")
      (node (ref "U1") (pin "34") (pinfunction "PC5_34") (pintype "bidirectional"))
    )
    (net (code "69") (name "unconnected-(U1B-PE7-Pad38)") (class "Default")
      (node (ref "U1") (pin "38") (pinfunction "PE7_38") (pintype "bidirectional"))
    )
    (net (code "70") (name "unconnected-(U1B-PE8-Pad39)") (class "Default")
      (node (ref "U1") (pin "39") (pinfunction "PE8_39") (pintype "bidirectional"))
    )
    (net (code "71") (name "unconnected-(U1B-PE9-Pad40)") (class "Default")
      (node (ref "U1") (pin "40") (pinfunction "PE9_40") (pintype "bidirectional"))
    )
    (net (code "72") (name "unconnected-(U1B-PE10-Pad41)") (class "Default")
      (node (ref "U1") (pin "41") (pinfunction "PE10_41") (pintype "bidirectional"))
    )
    (net (code "73") (name "unconnected-(U1B-PE11-Pad42)") (class "Default")
      (node (ref "U1") (pin "42") (pinfunction "PE11_42") (pintype "bidirectional"))
    )
    (net (code "74") (name "unconnected-(U1B-PE12-Pad43)") (class "Default")
      (node (ref "U1") (pin "43") (pinfunction "PE12_43") (pintype "bidirectional"))
    )
    (net (code "75") (name "unconnected-(U1B-PE13-Pad44)") (class "Default")
      (node (ref "U1") (pin "44") (pinfunction "PE13_44") (pintype "bidirectional"))
    )
    (net (code "76") (name "unconnected-(U1B-PE14-Pad45)") (class "Default")
      (node (ref "U1") (pin "45") (pinfunction "PE14_45") (pintype "bidirectional"))
    )
    (net (code "77") (name "unconnected-(U1B-PE15-Pad46)") (class "Default")
      (node (ref "U1") (pin "46") (pinfunction "PE15_46") (pintype "bidirectional"))
    )
    (net (code "78") (name "unconnected-(U1C-PA8{slash}USART1_CK{slash}I2C3_SCL-Pad67)") (class "Default")
      (node (ref "U1") (pin "67") (pinfunction "PA8/USART1_CK/I2C3_SCL_67") (pintype "bidirectional"))
    )
    (net (code "79") (name "unconnected-(U1C-PA9{slash}USART1_TX{slash}I2C3_SMBA-Pad68)") (class "Default")
      (node (ref "U1") (pin "68") (pinfunction "PA9/USART1_TX/I2C3_SMBA_68") (pintype "bidirectional"))
    )
    (net (code "80") (name "unconnected-(U1C-PA10{slash}USART1_RX-Pad69)") (class "Default")
      (node (ref "U1") (pin "69") (pinfunction "PA10/USART1_RX_69") (pintype "bidirectional"))
    )
    (net (code "81") (name "unconnected-(U1C-PB12{slash}SPI2_NSS{slash}I2C2_SMBA{slash}USART3_CK{slash}CAN2_RX-Pad51)") (class "Default")
      (node (ref "U1") (pin "51") (pinfunction "PB12/SPI2_NSS/I2C2_SMBA/USART3_CK/CAN2_RX_51") (pintype "bidirectional"))
    )
    (net (code "82") (name "unconnected-(U1C-PB13{slash}SPI2_SCK_USART3_CTS_CAN2_TX-Pad52)") (class "Default")
      (node (ref "U1") (pin "52") (pinfunction "PB13/SPI2_SCK_USART3_CTS_CAN2_TX_52") (pintype "bidirectional"))
    )
    (net (code "83") (name "unconnected-(U1C-PB14{slash}SPI2_MISO{slash}USART3_RTS-Pad53)") (class "Default")
      (node (ref "U1") (pin "53") (pinfunction "PB14/SPI2_MISO/USART3_RTS_53") (pintype "bidirectional"))
    )
    (net (code "84") (name "unconnected-(U1C-PB15{slash}SPI2_MOSI-Pad54)") (class "Default")
      (node (ref "U1") (pin "54") (pinfunction "PB15/SPI2_MOSI_54") (pintype "bidirectional"))
    )
    (net (code "85") (name "unconnected-(U1C-PC6{slash}USART6_TX-Pad63)") (class "Default")
      (node (ref "U1") (pin "63") (pinfunction "PC6/USART6_TX_63") (pintype "bidirectional"))
    )
    (net (code "86") (name "unconnected-(U1C-PC7{slash}USART6_RX-Pad64)") (class "Default")
      (node (ref "U1") (pin "64") (pinfunction "PC7/USART6_RX_64") (pintype "bidirectional"))
    )
    (net (code "87") (name "unconnected-(U1C-PC8{slash}USART6_CK-Pad65)") (class "Default")
      (node (ref "U1") (pin "65") (pinfunction "PC8/USART6_CK_65") (pintype "bidirectional"))
    )
    (net (code "88") (name "unconnected-(U1C-PC9{slash}I2C3_SDA-Pad66)") (class "Default")
      (node (ref "U1") (pin "66") (pinfunction "PC9/I2C3_SDA_66") (pintype "bidirectional"))
    )
    (net (code "89") (name "unconnected-(U1C-PD8{slash}USART3_TX-Pad55)") (class "Default")
      (node (ref "U1") (pin "55") (pinfunction "PD8/USART3_TX_55") (pintype "bidirectional"))
    )
    (net (code "90") (name "unconnected-(U1C-PD9{slash}USART3_RX-Pad56)") (class "Default")
      (node (ref "U1") (pin "56") (pinfunction "PD9/USART3_RX_56") (pintype "bidirectional"))
    )
    (net (code "91") (name "unconnected-(U1C-PD10{slash}USART3_CK-Pad57)") (class "Default")
      (node (ref "U1") (pin "57") (pinfunction "PD10/USART3_CK_57") (pintype "bidirectional"))
    )
    (net (code "92") (name "unconnected-(U1C-PD13-Pad60)") (class "Default")
      (node (ref "U1") (pin "60") (pinfunction "PD13_60") (pintype "bidirectional"))
    )
    (net (code "93") (name "unconnected-(U1C-PD14-Pad61)") (class "Default")
      (node (ref "U1") (pin "61") (pinfunction "PD14_61") (pintype "bidirectional"))
    )
    (net (code "94") (name "unconnected-(U1C-PD15-Pad62)") (class "Default")
      (node (ref "U1") (pin "62") (pinfunction "PD15_62") (pintype "bidirectional"))
    )
    (net (code "95") (name "unconnected-(U1D-PB5{slash}I2C1_SMBA{slash}CAN2_RX{slash}SPI1_MOSI{slash}SPI3_MOSI-Pad91)") (class "Default")
      (node (ref "U1") (pin "91") (pinfunction "PB5/I2C1_SMBA/CAN2_RX/SPI1_MOSI/SPI3_MOSI_91") (pintype "bidirectional"))
    )
    (net (code "96") (name "unconnected-(U1D-PB6{slash}I2C1_SCL{slash}CAN2_TX{slash}USART1_TX-Pad92)") (class "Default")
      (node (ref "U1") (pin "92") (pinfunction "PB6/I2C1_SCL/CAN2_TX/USART1_TX_92") (pintype "bidirectional"))
    )
    (net (code "97") (name "unconnected-(U1D-PB7{slash}I2C1_SDA{slash}USART1_RX-Pad93)") (class "Default")
      (node (ref "U1") (pin "93") (pinfunction "PB7/I2C1_SDA/USART1_RX_93") (pintype "bidirectional"))
    )
    (net (code "98") (name "unconnected-(U1D-PB8{slash}I2C1_SCL{slash}CAN1_RX-Pad95)") (class "Default")
      (node (ref "U1") (pin "95") (pinfunction "PB8/I2C1_SCL/CAN1_RX_95") (pintype "bidirectional"))
    )
    (net (code "99") (name "unconnected-(U1D-PB9{slash}I2C1_SDA{slash}SPI2_NSS{slash}CAN1_TX-Pad96)") (class "Default")
      (node (ref "U1") (pin "96") (pinfunction "PB9/I2C1_SDA/SPI2_NSS/CAN1_TX_96") (pintype "bidirectional"))
    )
    (net (code "100") (name "unconnected-(U1D-PC10{slash}SPI3_SCK{slash}UART4_TX{slash}USART3_CK-Pad78)") (class "Default")
      (node (ref "U1") (pin "78") (pinfunction "PC10/SPI3_SCK/UART4_TX/USART3_CK_78") (pintype "bidirectional"))
    )
    (net (code "101") (name "unconnected-(U1D-PC11{slash}UART4_RX{slash}SPI3_MISO{slash}USART3_RX-Pad79)") (class "Default")
      (node (ref "U1") (pin "79") (pinfunction "PC11/UART4_RX/SPI3_MISO/USART3_RX_79") (pintype "bidirectional"))
    )
    (net (code "102") (name "unconnected-(U1D-PC12{slash}UART5_TX{slash}SPI3_MOSI{slash}USART3_CK-Pad80)") (class "Default")
      (node (ref "U1") (pin "80") (pinfunction "PC12/UART5_TX/SPI3_MOSI/USART3_CK_80") (pintype "bidirectional"))
    )
    (net (code "103") (name "unconnected-(U1D-PD0{slash}CAN1_RX-Pad81)") (class "Default")
      (node (ref "U1") (pin "81") (pinfunction "PD0/CAN1_RX_81") (pintype "bidirectional"))
    )
    (net (code "104") (name "unconnected-(U1D-PD1{slash}CAN1_TX-Pad82)") (class "Default")
      (node (ref "U1") (pin "82") (pinfunction "PD1/CAN1_TX_82") (pintype "bidirectional"))
    )
    (net (code "105") (name "unconnected-(U1D-PD2{slash}UART5_RX-Pad83)") (class "Default")
      (node (ref "U1") (pin "83") (pinfunction "PD2/UART5_RX_83") (pintype "bidirectional"))
    )
    (net (code "106") (name "unconnected-(U1D-PD3{slash}USART2_CTS-Pad84)") (class "Default")
      (node (ref "U1") (pin "84") (pinfunction "PD3/USART2_CTS_84") (pintype "bidirectional"))
    )
    (net (code "107") (name "unconnected-(U1D-PD4{slash}USART2_RTS-Pad85)") (class "Default")
      (node (ref "U1") (pin "85") (pinfunction "PD4/USART2_RTS_85") (pintype "bidirectional"))
    )
    (net (code "108") (name "unconnected-(U1D-PD5{slash}USART2_TX-Pad86)") (class "Default")
      (node (ref "U1") (pin "86") (pinfunction "PD5/USART2_TX_86") (pintype "bidirectional"))
    )
    (net (code "109") (name "unconnected-(U1D-PD6{slash}USART2_RX-Pad87)") (class "Default")
      (node (ref "U1") (pin "87") (pinfunction "PD6/USART2_RX_87") (pintype "bidirectional"))
    )
    (net (code "110") (name "unconnected-(U1D-PD7{slash}USART2_CK-Pad88)") (class "Default")
      (node (ref "U1") (pin "88") (pinfunction "PD7/USART2_CK_88") (pintype "bidirectional"))
    )
    (net (code "111") (name "unconnected-(U1D-PE0-Pad97)") (class "Default")
      (node (ref "U1") (pin "97") (pinfunction "PE0_97") (pintype "bidirectional"))
    )
    (net (code "112") (name "unconnected-(U1D-PE1-Pad98)") (class "Default")
      (node (ref "U1") (pin "98") (pinfunction "PE1_98") (pintype "bidirectional"))
    )
  )
)
